# Sitara_IO_Bank_45.net
KiCad netlist of a schematic drawn in Altium Designer
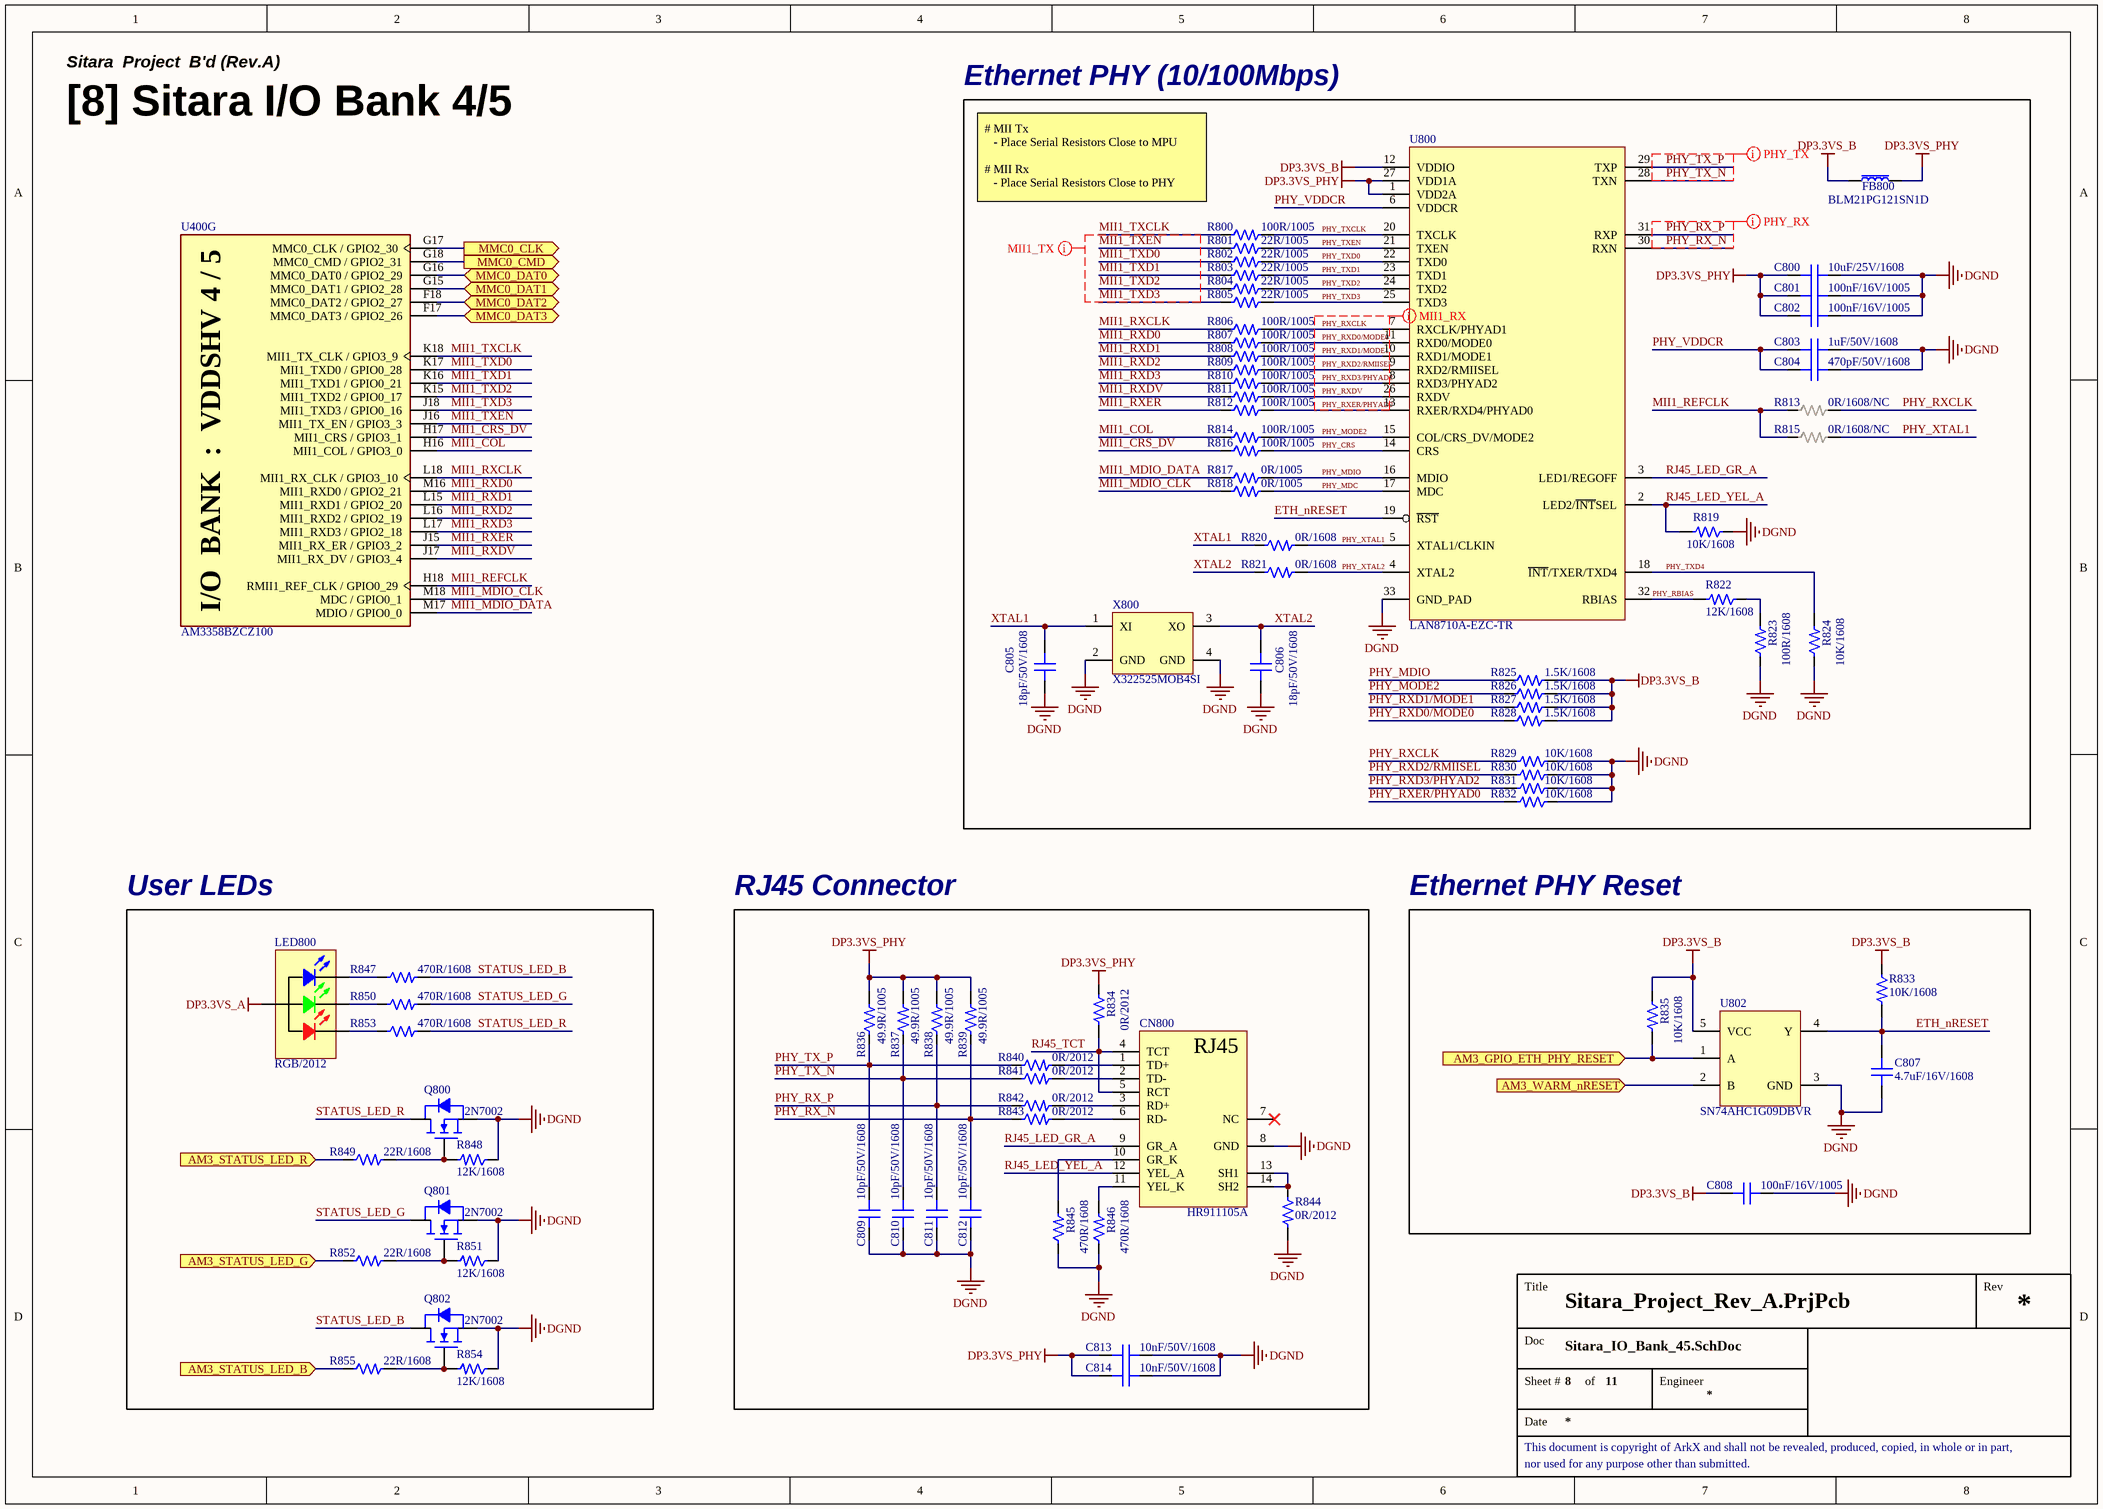
[diagram p0: Sitara_IO_Bank_45.SchDoc]

(export (version "E")
  (design (tool "Eeschema 10.0.6"))
  (components
    (comp (ref "C800")
      (value "10uF/25V/1608")
      (footprint "CAP 1608 (0603_INCH)")
      (description "Ceramic CAP_10uF/25V/1608")
      (fields (field (name "LCSC PART #") "C96446"))
      (libsource (lib "Arkx") (part "CAP_10uF/25V/1608"))
    )
    (comp (ref "C801")
      (value "100nF/16V/1005")
      (footprint "CAP 1005 (0402_INCH)")
      (description "Ceramic CAP_100nF/16V/1005")
      (fields (field (name "LCSC PART #") "C1525"))
      (libsource (lib "Arkx") (part "CAP_100nF/16V/1005"))
    )
    (comp (ref "C802")
      (value "100nF/16V/1005")
      (footprint "CAP 1005 (0402_INCH)")
      (description "Ceramic CAP_100nF/16V/1005")
      (fields (field (name "LCSC PART #") "C1525"))
      (libsource (lib "Arkx") (part "CAP_100nF/16V/1005"))
    )
    (comp (ref "C803")
      (value "1uF/50V/1608")
      (footprint "CAP 1608 (0603_INCH)")
      (description "Ceramic CAP_1uF/50V/1608")
      (fields (field (name "LCSC PART #") "C15849"))
      (libsource (lib "Arkx") (part "CAP_1uF/50V/1608"))
    )
    (comp (ref "C804")
      (value "470pF/50V/1608")
      (footprint "CAP 1608 (0603_INCH)")
      (description "Ceramic CAP_470pF/50V/1608")
      (fields (field (name "LCSC PART #") "C1620"))
      (libsource (lib "Arkx") (part "CAP_470pF/50V/1608"))
    )
    (comp (ref "C805")
      (value "18pF/50V/1608")
      (footprint "CAP 1608 (0603_INCH)")
      (description "Ceramic CAP_18pF/50V/1608")
      (fields (field (name "LCSC PART #") "C1647"))
      (libsource (lib "Arkx") (part "CAP_18pF/50V/1608"))
    )
    (comp (ref "C806")
      (value "18pF/50V/1608")
      (footprint "CAP 1608 (0603_INCH)")
      (description "Ceramic CAP_18pF/50V/1608")
      (fields (field (name "LCSC PART #") "C1647"))
      (libsource (lib "Arkx") (part "CAP_18pF/50V/1608"))
    )
    (comp (ref "C807")
      (value "4.7uF/16V/1608")
      (footprint "CAP 1608 (0603_INCH)")
      (description "Ceramic CAP_4.7uF/16V/1608")
      (fields (field (name "LCSC PART #") "C19666"))
      (libsource (lib "Arkx") (part "CAP_4.7uF/16V/1608"))
    )
    (comp (ref "C808")
      (value "100nF/16V/1005")
      (footprint "CAP 1005 (0402_INCH)")
      (description "Ceramic CAP_100nF/16V/1005")
      (fields (field (name "LCSC PART #") "C1525"))
      (libsource (lib "Arkx") (part "CAP_100nF/16V/1005"))
    )
    (comp (ref "C809")
      (value "10pF/50V/1608")
      (footprint "CAP 1608 (0603_INCH)")
      (description "Ceramic CAP_10pF/50V/1608")
      (fields (field (name "LCSC PART #") "C1634"))
      (libsource (lib "Arkx") (part "CAP_10pF/50V/1608"))
    )
    (comp (ref "C810")
      (value "10pF/50V/1608")
      (footprint "CAP 1608 (0603_INCH)")
      (description "Ceramic CAP_10pF/50V/1608")
      (fields (field (name "LCSC PART #") "C1634"))
      (libsource (lib "Arkx") (part "CAP_10pF/50V/1608"))
    )
    (comp (ref "C811")
      (value "10pF/50V/1608")
      (footprint "CAP 1608 (0603_INCH)")
      (description "Ceramic CAP_10pF/50V/1608")
      (fields (field (name "LCSC PART #") "C1634"))
      (libsource (lib "Arkx") (part "CAP_10pF/50V/1608"))
    )
    (comp (ref "C812")
      (value "10pF/50V/1608")
      (footprint "CAP 1608 (0603_INCH)")
      (description "Ceramic CAP_10pF/50V/1608")
      (fields (field (name "LCSC PART #") "C1634"))
      (libsource (lib "Arkx") (part "CAP_10pF/50V/1608"))
    )
    (comp (ref "C813")
      (value "10nF/50V/1608")
      (footprint "CAP 1608 (0603_INCH)")
      (description "Ceramic CAP_10nF/50V/1608")
      (fields (field (name "LCSC PART #") "C57112"))
      (libsource (lib "Arkx") (part "CAP_10nF/50V/1608"))
    )
    (comp (ref "C814")
      (value "10nF/50V/1608")
      (footprint "CAP 1608 (0603_INCH)")
      (description "Ceramic CAP_10nF/50V/1608")
      (fields (field (name "LCSC PART #") "C57112"))
      (libsource (lib "Arkx") (part "CAP_10nF/50V/1608"))
    )
    (comp (ref "CN800")
      (value "HR911105A")
      (footprint "CON_RJ45")
      (description "RJ45Receptacle 1 WithLED Plugin Ethernet Connectors / Modular Connectors (RJ45 RJ11) ROHS")
      (fields (field (name "LCSC PART #") "C12074"))
      (libsource (lib "Arkx") (part "CON_RJ45_HR911105A"))
    )
    (comp (ref "FB800")
      (value "BLM21PG121SN1D")
      (footprint "FB 2012 (0805_inch)")
      (description "3A 1 30mΩ 120Ω@100MHz ±25% 0805  Ferrite Beads ROHS")
      (fields (field (name "LCSC PART #") "C79382"))
      (libsource (lib "Arkx") (part "FB_BLM21PG121SN1D"))
    )
    (comp (ref "LED800")
      (value "RGB/2012")
      (footprint "LED MHT170RGBCT")
      (fields (field (name "LCSC PART #") "C2962094"))
      (libsource (lib "Arkx") (part "LED_RGB_MHT170RGBCT"))
    )
    (comp (ref "Q800")
      (value "2N7002")
      (footprint "SOT 23-3 (DIODES INCORPORATED)")
      (description "60V 115mA 200mW 7.5Ω@10V,500mA N Channel SOT-23  MOSFETs ROHS")
      (fields (field (name "LCSC PART #") "C8545"))
      (libsource (lib "Arkx") (part "FET_2N7002"))
    )
    (comp (ref "Q801")
      (value "2N7002")
      (footprint "SOT 23-3 (DIODES INCORPORATED)")
      (description "60V 115mA 200mW 7.5Ω@10V,500mA N Channel SOT-23  MOSFETs ROHS")
      (fields (field (name "LCSC PART #") "C8545"))
      (libsource (lib "Arkx") (part "FET_2N7002"))
    )
    (comp (ref "Q802")
      (value "2N7002")
      (footprint "SOT 23-3 (DIODES INCORPORATED)")
      (description "60V 115mA 200mW 7.5Ω@10V,500mA N Channel SOT-23  MOSFETs ROHS")
      (fields (field (name "LCSC PART #") "C8545"))
      (libsource (lib "Arkx") (part "FET_2N7002"))
    )
    (comp (ref "R800")
      (value "100R/1005")
      (footprint "RES 1005 (0402_inch)")
      (description "RES_100R/1005/62.5mW")
      (fields (field (name "LCSC PART #") "C25076"))
      (libsource (lib "Arkx") (part "RES_100R/1005/62.5mW"))
    )
    (comp (ref "R801")
      (value "22R/1005")
      (footprint "RES 1005 (0402_inch)")
      (description "RES_22R/1005/62.5mW")
      (fields (field (name "LCSC PART #") "C25092"))
      (libsource (lib "Arkx") (part "RES_22R/1005/62.5mW"))
    )
    (comp (ref "R802")
      (value "22R/1005")
      (footprint "RES 1005 (0402_inch)")
      (description "RES_22R/1005/62.5mW")
      (fields (field (name "LCSC PART #") "C25092"))
      (libsource (lib "Arkx") (part "RES_22R/1005/62.5mW"))
    )
    (comp (ref "R803")
      (value "22R/1005")
      (footprint "RES 1005 (0402_inch)")
      (description "RES_22R/1005/62.5mW")
      (fields (field (name "LCSC PART #") "C25092"))
      (libsource (lib "Arkx") (part "RES_22R/1005/62.5mW"))
    )
    (comp (ref "R804")
      (value "22R/1005")
      (footprint "RES 1005 (0402_inch)")
      (description "RES_22R/1005/62.5mW")
      (fields (field (name "LCSC PART #") "C25092"))
      (libsource (lib "Arkx") (part "RES_22R/1005/62.5mW"))
    )
    (comp (ref "R805")
      (value "22R/1005")
      (footprint "RES 1005 (0402_inch)")
      (description "RES_22R/1005/62.5mW")
      (fields (field (name "LCSC PART #") "C25092"))
      (libsource (lib "Arkx") (part "RES_22R/1005/62.5mW"))
    )
    (comp (ref "R806")
      (value "100R/1005")
      (footprint "RES 1005 (0402_inch)")
      (description "RES_100R/1005/62.5mW")
      (fields (field (name "LCSC PART #") "C25076"))
      (libsource (lib "Arkx") (part "RES_100R/1005/62.5mW"))
    )
    (comp (ref "R807")
      (value "100R/1005")
      (footprint "RES 1005 (0402_inch)")
      (description "RES_100R/1005/62.5mW")
      (fields (field (name "LCSC PART #") "C25076"))
      (libsource (lib "Arkx") (part "RES_100R/1005/62.5mW"))
    )
    (comp (ref "R808")
      (value "100R/1005")
      (footprint "RES 1005 (0402_inch)")
      (description "RES_100R/1005/62.5mW")
      (fields (field (name "LCSC PART #") "C25076"))
      (libsource (lib "Arkx") (part "RES_100R/1005/62.5mW"))
    )
    (comp (ref "R809")
      (value "100R/1005")
      (footprint "RES 1005 (0402_inch)")
      (description "RES_100R/1005/62.5mW")
      (fields (field (name "LCSC PART #") "C25076"))
      (libsource (lib "Arkx") (part "RES_100R/1005/62.5mW"))
    )
    (comp (ref "R810")
      (value "100R/1005")
      (footprint "RES 1005 (0402_inch)")
      (description "RES_100R/1005/62.5mW")
      (fields (field (name "LCSC PART #") "C25076"))
      (libsource (lib "Arkx") (part "RES_100R/1005/62.5mW"))
    )
    (comp (ref "R811")
      (value "100R/1005")
      (footprint "RES 1005 (0402_inch)")
      (description "RES_100R/1005/62.5mW")
      (fields (field (name "LCSC PART #") "C25076"))
      (libsource (lib "Arkx") (part "RES_100R/1005/62.5mW"))
    )
    (comp (ref "R812")
      (value "100R/1005")
      (footprint "RES 1005 (0402_inch)")
      (description "RES_100R/1005/62.5mW")
      (fields (field (name "LCSC PART #") "C25076"))
      (libsource (lib "Arkx") (part "RES_100R/1005/62.5mW"))
    )
    (comp (ref "R813")
      (value "0R/1608/NC")
      (footprint "RES 1608 (0603_inch)/NC")
      (description "0R/1608/0.1W/NC")
      (libsource (lib "Arkx") (part "RES_NC_0R/1608/0.1W"))
    )
    (comp (ref "R814")
      (value "100R/1005")
      (footprint "RES 1005 (0402_inch)")
      (description "RES_100R/1005/62.5mW")
      (fields (field (name "LCSC PART #") "C25076"))
      (libsource (lib "Arkx") (part "RES_100R/1005/62.5mW"))
    )
    (comp (ref "R815")
      (value "0R/1608/NC")
      (footprint "RES 1608 (0603_inch)/NC")
      (description "0R/1608/0.1W/NC")
      (libsource (lib "Arkx") (part "RES_NC_0R/1608/0.1W"))
    )
    (comp (ref "R816")
      (value "100R/1005")
      (footprint "RES 1005 (0402_inch)")
      (description "RES_100R/1005/62.5mW")
      (fields (field (name "LCSC PART #") "C25076"))
      (libsource (lib "Arkx") (part "RES_100R/1005/62.5mW"))
    )
    (comp (ref "R817")
      (value "0R/1005")
      (footprint "RES 1005 (0402_inch)")
      (description "RES_0R/1005/62.5mW")
      (fields (field (name "LCSC PART #") "C17168"))
      (libsource (lib "Arkx") (part "RES_0R/1005/62.5mW"))
    )
    (comp (ref "R818")
      (value "0R/1005")
      (footprint "RES 1005 (0402_inch)")
      (description "RES_0R/1005/62.5mW")
      (fields (field (name "LCSC PART #") "C17168"))
      (libsource (lib "Arkx") (part "RES_0R/1005/62.5mW"))
    )
    (comp (ref "R819")
      (value "10K/1608")
      (footprint "RES 1608 (0603_inch)")
      (description "RES_10K/1608/0.1W")
      (fields (field (name "LCSC PART #") "C25804"))
      (libsource (lib "Arkx") (part "RES_10K/1608/0.1W"))
    )
    (comp (ref "R820")
      (value "0R/1608")
      (footprint "RES 1608 (0603_inch)")
      (description "RES_0R/1608/0.1W")
      (fields (field (name "LCSC PART #") "C21189"))
      (libsource (lib "Arkx") (part "RES_0R/1608/0.1W"))
    )
    (comp (ref "R821")
      (value "0R/1608")
      (footprint "RES 1608 (0603_inch)")
      (description "RES_0R/1608/0.1W")
      (fields (field (name "LCSC PART #") "C21189"))
      (libsource (lib "Arkx") (part "RES_0R/1608/0.1W"))
    )
    (comp (ref "R822")
      (value "12K/1608")
      (footprint "RES 1608 (0603_inch)")
      (description "RES_12K/1608/0.1W")
      (fields (field (name "LCSC PART #") "C22790"))
      (libsource (lib "Arkx") (part "RES_12K/1608/0.1W"))
    )
    (comp (ref "R823")
      (value "100R/1608")
      (footprint "RES 1608 (0603_inch)")
      (description "RES_100R/1608/0.1W")
      (fields (field (name "LCSC PART #") "C22775"))
      (libsource (lib "Arkx") (part "RES_100R/1608/0.1W"))
    )
    (comp (ref "R824")
      (value "10K/1608")
      (footprint "RES 1608 (0603_inch)")
      (description "RES_10K/1608/0.1W")
      (fields (field (name "LCSC PART #") "C25804"))
      (libsource (lib "Arkx") (part "RES_10K/1608/0.1W"))
    )
    (comp (ref "R825")
      (value "1.5K/1608")
      (footprint "RES 1608 (0603_inch)")
      (description "RES_1.5K/1608/0.1W")
      (fields (field (name "LCSC PART #") "C22843"))
      (libsource (lib "Arkx") (part "RES_1.5K/1608/0.1W"))
    )
    (comp (ref "R826")
      (value "1.5K/1608")
      (footprint "RES 1608 (0603_inch)")
      (description "RES_1.5K/1608/0.1W")
      (fields (field (name "LCSC PART #") "C22843"))
      (libsource (lib "Arkx") (part "RES_1.5K/1608/0.1W"))
    )
    (comp (ref "R827")
      (value "1.5K/1608")
      (footprint "RES 1608 (0603_inch)")
      (description "RES_1.5K/1608/0.1W")
      (fields (field (name "LCSC PART #") "C22843"))
      (libsource (lib "Arkx") (part "RES_1.5K/1608/0.1W"))
    )
    (comp (ref "R828")
      (value "1.5K/1608")
      (footprint "RES 1608 (0603_inch)")
      (description "RES_1.5K/1608/0.1W")
      (fields (field (name "LCSC PART #") "C22843"))
      (libsource (lib "Arkx") (part "RES_1.5K/1608/0.1W"))
    )
    (comp (ref "R829")
      (value "10K/1608")
      (footprint "RES 1608 (0603_inch)")
      (description "RES_10K/1608/0.1W")
      (fields (field (name "LCSC PART #") "C25804"))
      (libsource (lib "Arkx") (part "RES_10K/1608/0.1W"))
    )
    (comp (ref "R830")
      (value "10K/1608")
      (footprint "RES 1608 (0603_inch)")
      (description "RES_10K/1608/0.1W")
      (fields (field (name "LCSC PART #") "C25804"))
      (libsource (lib "Arkx") (part "RES_10K/1608/0.1W"))
    )
    (comp (ref "R831")
      (value "10K/1608")
      (footprint "RES 1608 (0603_inch)")
      (description "RES_10K/1608/0.1W")
      (fields (field (name "LCSC PART #") "C25804"))
      (libsource (lib "Arkx") (part "RES_10K/1608/0.1W"))
    )
    (comp (ref "R832")
      (value "10K/1608")
      (footprint "RES 1608 (0603_inch)")
      (description "RES_10K/1608/0.1W")
      (fields (field (name "LCSC PART #") "C25804"))
      (libsource (lib "Arkx") (part "RES_10K/1608/0.1W"))
    )
    (comp (ref "R833")
      (value "10K/1608")
      (footprint "RES 1608 (0603_inch)")
      (description "RES_10K/1608/0.1W")
      (fields (field (name "LCSC PART #") "C25804"))
      (libsource (lib "Arkx") (part "RES_10K/1608/0.1W"))
    )
    (comp (ref "R834")
      (value "0R/2012")
      (footprint "RES 2012 (0805_inch)")
      (description "RES_0R/2012/0.125W")
      (fields (field (name "LCSC PART #") "C17477"))
      (libsource (lib "Arkx") (part "RES_0R/2012/0.125W"))
    )
    (comp (ref "R835")
      (value "10K/1608")
      (footprint "RES 1608 (0603_inch)")
      (description "RES_10K/1608/0.1W")
      (fields (field (name "LCSC PART #") "C25804"))
      (libsource (lib "Arkx") (part "RES_10K/1608/0.1W"))
    )
    (comp (ref "R836")
      (value "49.9R/1005")
      (footprint "RES 1005 (0402_inch)")
      (description "RES_49.9R/1005/62.5mW")
      (fields (field (name "LCSC PART #") "C25120"))
      (libsource (lib "Arkx") (part "RES_49.9R/1005/62.5mW"))
    )
    (comp (ref "R837")
      (value "49.9R/1005")
      (footprint "RES 1005 (0402_inch)")
      (description "RES_49.9R/1005/62.5mW")
      (fields (field (name "LCSC PART #") "C25120"))
      (libsource (lib "Arkx") (part "RES_49.9R/1005/62.5mW"))
    )
    (comp (ref "R838")
      (value "49.9R/1005")
      (footprint "RES 1005 (0402_inch)")
      (description "RES_49.9R/1005/62.5mW")
      (fields (field (name "LCSC PART #") "C25120"))
      (libsource (lib "Arkx") (part "RES_49.9R/1005/62.5mW"))
    )
    (comp (ref "R839")
      (value "49.9R/1005")
      (footprint "RES 1005 (0402_inch)")
      (description "RES_49.9R/1005/62.5mW")
      (fields (field (name "LCSC PART #") "C25120"))
      (libsource (lib "Arkx") (part "RES_49.9R/1005/62.5mW"))
    )
    (comp (ref "R840")
      (value "0R/2012")
      (footprint "RES 2012 (0805_inch)")
      (description "RES_0R/2012/0.125W")
      (fields (field (name "LCSC PART #") "C17477"))
      (libsource (lib "Arkx") (part "RES_0R/2012/0.125W"))
    )
    (comp (ref "R841")
      (value "0R/2012")
      (footprint "RES 2012 (0805_inch)")
      (description "RES_0R/2012/0.125W")
      (fields (field (name "LCSC PART #") "C17477"))
      (libsource (lib "Arkx") (part "RES_0R/2012/0.125W"))
    )
    (comp (ref "R842")
      (value "0R/2012")
      (footprint "RES 2012 (0805_inch)")
      (description "RES_0R/2012/0.125W")
      (fields (field (name "LCSC PART #") "C17477"))
      (libsource (lib "Arkx") (part "RES_0R/2012/0.125W"))
    )
    (comp (ref "R843")
      (value "0R/2012")
      (footprint "RES 2012 (0805_inch)")
      (description "RES_0R/2012/0.125W")
      (fields (field (name "LCSC PART #") "C17477"))
      (libsource (lib "Arkx") (part "RES_0R/2012/0.125W"))
    )
    (comp (ref "R844")
      (value "0R/2012")
      (footprint "RES 2012 (0805_inch)")
      (description "RES_0R/2012/0.125W")
      (fields (field (name "LCSC PART #") "C17477"))
      (libsource (lib "Arkx") (part "RES_0R/2012/0.125W"))
    )
    (comp (ref "R845")
      (value "470R/1608")
      (footprint "RES 1608 (0603_inch)")
      (description "RES_470R/1608/0.1W")
      (fields (field (name "LCSC PART #") "C23179"))
      (libsource (lib "Arkx") (part "RES_470R/1608/0.1W"))
    )
    (comp (ref "R846")
      (value "470R/1608")
      (footprint "RES 1608 (0603_inch)")
      (description "RES_470R/1608/0.1W")
      (fields (field (name "LCSC PART #") "C23179"))
      (libsource (lib "Arkx") (part "RES_470R/1608/0.1W"))
    )
    (comp (ref "R847")
      (value "470R/1608")
      (footprint "RES 1608 (0603_inch)")
      (description "RES_470R/1608/0.1W")
      (fields (field (name "LCSC PART #") "C23179"))
      (libsource (lib "Arkx") (part "RES_470R/1608/0.1W"))
    )
    (comp (ref "R848")
      (value "12K/1608")
      (footprint "RES 1608 (0603_inch)")
      (description "RES_12K/1608/0.1W")
      (fields (field (name "LCSC PART #") "C22790"))
      (libsource (lib "Arkx") (part "RES_12K/1608/0.1W"))
    )
    (comp (ref "R849")
      (value "22R/1608")
      (footprint "RES 1608 (0603_inch)")
      (description "RES_22R/1608/0.1W")
      (fields (field (name "LCSC PART #") "C23345"))
      (libsource (lib "Arkx") (part "RES_22R/1608/0.1W"))
    )
    (comp (ref "R850")
      (value "470R/1608")
      (footprint "RES 1608 (0603_inch)")
      (description "RES_470R/1608/0.1W")
      (fields (field (name "LCSC PART #") "C23179"))
      (libsource (lib "Arkx") (part "RES_470R/1608/0.1W"))
    )
    (comp (ref "R851")
      (value "12K/1608")
      (footprint "RES 1608 (0603_inch)")
      (description "RES_12K/1608/0.1W")
      (fields (field (name "LCSC PART #") "C22790"))
      (libsource (lib "Arkx") (part "RES_12K/1608/0.1W"))
    )
    (comp (ref "R852")
      (value "22R/1608")
      (footprint "RES 1608 (0603_inch)")
      (description "RES_22R/1608/0.1W")
      (fields (field (name "LCSC PART #") "C23345"))
      (libsource (lib "Arkx") (part "RES_22R/1608/0.1W"))
    )
    (comp (ref "R853")
      (value "470R/1608")
      (footprint "RES 1608 (0603_inch)")
      (description "RES_470R/1608/0.1W")
      (fields (field (name "LCSC PART #") "C23179"))
      (libsource (lib "Arkx") (part "RES_470R/1608/0.1W"))
    )
    (comp (ref "R854")
      (value "12K/1608")
      (footprint "RES 1608 (0603_inch)")
      (description "RES_12K/1608/0.1W")
      (fields (field (name "LCSC PART #") "C22790"))
      (libsource (lib "Arkx") (part "RES_12K/1608/0.1W"))
    )
    (comp (ref "R855")
      (value "22R/1608")
      (footprint "RES 1608 (0603_inch)")
      (description "RES_22R/1608/0.1W")
      (fields (field (name "LCSC PART #") "C23345"))
      (libsource (lib "Arkx") (part "RES_22R/1608/0.1W"))
    )
    (comp (ref "U400")
      (value "AM3358BZCZ100")
      (footprint "IC_SOC_AM3358BZCZ100")
      (description "ARM® Cortex®-A8 Microprocessor IC Sitara™ 1 Core, 32-Bit 1.0GHz 324-NFBGA (15x15)")
      (fields (field (name "LCSC PART #") "C73932"))
      (libsource (lib "Arkx") (part "IC_SOC_AM3358BZCZ100"))
    )
    (comp (ref "U800")
      (value "LAN8710A-EZC-TR")
      (footprint "IC_QFN-32 (5x5)")
      (description "4/4 Transceiver Full MII, RMII 32-QFN (5x5)")
      (fields (field (name "LCSC PART #") "C46185"))
      (libsource (lib "Arkx") (part "IC_ETH_LAN8710A-EZC-TR"))
    )
    (comp (ref "U802")
      (value "SN74AHC1G09DBVR")
      (footprint "SOT-23-5 (TI DBV PACKAGE)")
      (description "AND Gate IC 1 Channel Open Drain SOT-23-5")
      (fields (field (name "LCSC PART #") "C840099"))
      (libsource (lib "Arkx") (part "IC_AND_SN74AHC1G09DBVR"))
    )
    (comp (ref "X800")
      (value "X322525MOB4SI")
      (footprint "OSC_SMD_3.2x2.5(YXC)")
      (description "25MHz Surface Mount Crystal 12pF ±10ppm ±20ppm SMD3225-4P Crystals ROHS")
      (fields (field (name "LCSC PART #") "C9006"))
      (libsource (lib "Arkx") (part "XTAL_25MHz_X322525MOB4SI"))
    )
  )
  (nets
    (net (code "1") (name "/AM3_GPIO_ETH_PHY_RESET") (class "Default")
      (node (ref "R835") (pin "2") (pinfunction "2_2") (pintype "passive"))
      (node (ref "U802") (pin "1") (pinfunction "A_1") (pintype "passive"))
    )
    (net (code "2") (name "/AM3_STATUS_LED_B") (class "Default")
      (node (ref "R855") (pin "1") (pinfunction "1_1") (pintype "passive"))
    )
    (net (code "3") (name "/AM3_STATUS_LED_G") (class "Default")
      (node (ref "R852") (pin "1") (pinfunction "1_1") (pintype "passive"))
    )
    (net (code "4") (name "/AM3_STATUS_LED_R") (class "Default")
      (node (ref "R849") (pin "1") (pinfunction "1_1") (pintype "passive"))
    )
    (net (code "5") (name "/AM3_WARM_nRESET") (class "Default")
      (node (ref "U802") (pin "2") (pinfunction "B_2") (pintype "passive"))
    )
    (net (code "6") (name "/ETH_nRESET") (class "Default")
      (node (ref "C807") (pin "2") (pinfunction "2_2") (pintype "passive"))
      (node (ref "R833") (pin "2") (pinfunction "2_2") (pintype "passive"))
      (node (ref "U800") (pin "19") (pinfunction "~{RST}_19") (pintype "passive"))
      (node (ref "U802") (pin "4") (pinfunction "Y_4") (pintype "passive"))
    )
    (net (code "7") (name "/MII1_COL") (class "Default")
      (node (ref "R814") (pin "1") (pinfunction "1_1") (pintype "passive"))
      (node (ref "U400") (pin "H16") (pinfunction "MII1_COL_/_GPIO3_0_H16") (pintype "passive"))
    )
    (net (code "8") (name "/MII1_CRS_DV") (class "Default")
      (node (ref "R816") (pin "1") (pinfunction "1_1") (pintype "passive"))
      (node (ref "U400") (pin "H17") (pinfunction "MII1_CRS_/_GPIO3_1_H17") (pintype "passive"))
    )
    (net (code "9") (name "/MII1_MDIO_CLK") (class "Default")
      (node (ref "R818") (pin "1") (pinfunction "1_1") (pintype "passive"))
      (node (ref "U400") (pin "M18") (pinfunction "MDC_/_GPIO0_1_M18") (pintype "passive"))
    )
    (net (code "10") (name "/MII1_MDIO_DATA") (class "Default")
      (node (ref "R817") (pin "1") (pinfunction "1_1") (pintype "passive"))
      (node (ref "U400") (pin "M17") (pinfunction "MDIO_/_GPIO0_0_M17") (pintype "passive"))
    )
    (net (code "11") (name "/MII1_REFCLK") (class "Default")
      (node (ref "R813") (pin "1") (pinfunction "1_1") (pintype "passive"))
      (node (ref "R815") (pin "1") (pinfunction "1_1") (pintype "passive"))
      (node (ref "U400") (pin "H18") (pinfunction "RMII1_REF_CLK_/_GPIO0_29_H18") (pintype "passive"))
    )
    (net (code "12") (name "/MII1_RXCLK") (class "Default")
      (node (ref "R806") (pin "1") (pinfunction "1_1") (pintype "passive"))
      (node (ref "U400") (pin "L18") (pinfunction "MII1_RX_CLK_/_GPIO3_10_L18") (pintype "passive"))
    )
    (net (code "13") (name "/MII1_RXD0") (class "Default")
      (node (ref "R807") (pin "1") (pinfunction "1_1") (pintype "passive"))
      (node (ref "U400") (pin "M16") (pinfunction "MII1_RXD0_/_GPIO2_21_M16") (pintype "passive"))
    )
    (net (code "14") (name "/MII1_RXD1") (class "Default")
      (node (ref "R808") (pin "1") (pinfunction "1_1") (pintype "passive"))
      (node (ref "U400") (pin "L15") (pinfunction "MII1_RXD1_/_GPIO2_20_L15") (pintype "passive"))
    )
    (net (code "15") (name "/MII1_RXD2") (class "Default")
      (node (ref "R809") (pin "1") (pinfunction "1_1") (pintype "passive"))
      (node (ref "U400") (pin "L16") (pinfunction "MII1_RXD2_/_GPIO2_19_L16") (pintype "passive"))
    )
    (net (code "16") (name "/MII1_RXD3") (class "Default")
      (node (ref "R810") (pin "1") (pinfunction "1_1") (pintype "passive"))
      (node (ref "U400") (pin "L17") (pinfunction "MII1_RXD3_/_GPIO2_18_L17") (pintype "passive"))
    )
    (net (code "17") (name "/MII1_RXDV") (class "Default")
      (node (ref "R811") (pin "1") (pinfunction "1_1") (pintype "passive"))
      (node (ref "U400") (pin "J17") (pinfunction "MII1_RX_DV_/_GPIO3_4_J17") (pintype "passive"))
    )
    (net (code "18") (name "/MII1_RXER") (class "Default")
      (node (ref "R812") (pin "1") (pinfunction "1_1") (pintype "passive"))
      (node (ref "U400") (pin "J15") (pinfunction "MII1_RX_ER_/_GPIO3_2_J15") (pintype "passive"))
    )
    (net (code "19") (name "/MII1_TXCLK") (class "Default")
      (node (ref "R800") (pin "1") (pinfunction "1_1") (pintype "passive"))
      (node (ref "U400") (pin "K18") (pinfunction "MII1_TX_CLK_/_GPIO3_9_K18") (pintype "passive"))
    )
    (net (code "20") (name "/MII1_TXD0") (class "Default")
      (node (ref "R802") (pin "1") (pinfunction "1_1") (pintype "passive"))
      (node (ref "U400") (pin "K17") (pinfunction "MII1_TXD0_/_GPIO0_28_K17") (pintype "passive"))
    )
    (net (code "21") (name "/MII1_TXD1") (class "Default")
      (node (ref "R803") (pin "1") (pinfunction "1_1") (pintype "passive"))
      (node (ref "U400") (pin "K16") (pinfunction "MII1_TXD1_/_GPIO0_21_K16") (pintype "passive"))
    )
    (net (code "22") (name "/MII1_TXD2") (class "Default")
      (node (ref "R804") (pin "1") (pinfunction "1_1") (pintype "passive"))
      (node (ref "U400") (pin "K15") (pinfunction "MII1_TXD2_/_GPIO0_17_K15") (pintype "passive"))
    )
    (net (code "23") (name "/MII1_TXD3") (class "Default")
      (node (ref "R805") (pin "1") (pinfunction "1_1") (pintype "passive"))
      (node (ref "U400") (pin "J18") (pinfunction "MII1_TXD3_/_GPIO0_16_J18") (pintype "passive"))
    )
    (net (code "24") (name "/MII1_TXEN") (class "Default")
      (node (ref "R801") (pin "1") (pinfunction "1_1") (pintype "passive"))
      (node (ref "U400") (pin "J16") (pinfunction "MII1_TX_EN_/_GPIO3_3_J16") (pintype "passive"))
    )
    (net (code "25") (name "/MMC0_CLK") (class "Default")
      (node (ref "U400") (pin "G17") (pinfunction "MMC0_CLK_/_GPIO2_30_G17") (pintype "passive"))
    )
    (net (code "26") (name "/MMC0_CMD") (class "Default")
      (node (ref "U400") (pin "G18") (pinfunction "MMC0_CMD_/_GPIO2_31_G18") (pintype "passive"))
    )
    (net (code "27") (name "/MMC0_DAT0") (class "Default")
      (node (ref "U400") (pin "G16") (pinfunction "MMC0_DAT0_/_GPIO2_29_G16") (pintype "passive"))
    )
    (net (code "28") (name "/MMC0_DAT1") (class "Default")
      (node (ref "U400") (pin "G15") (pinfunction "MMC0_DAT1_/_GPIO2_28_G15") (pintype "passive"))
    )
    (net (code "29") (name "/MMC0_DAT2") (class "Default")
      (node (ref "U400") (pin "F18") (pinfunction "MMC0_DAT2_/_GPIO2_27_F18") (pintype "passive"))
    )
    (net (code "30") (name "/MMC0_DAT3") (class "Default")
      (node (ref "U400") (pin "F17") (pinfunction "MMC0_DAT3_/_GPIO2_26_F17") (pintype "passive"))
    )
    (net (code "31") (name "/PHY_CRS") (class "Default")
      (node (ref "R816") (pin "2") (pinfunction "2_2") (pintype "passive"))
      (node (ref "U800") (pin "14") (pinfunction "CRS_14") (pintype "passive"))
    )
    (net (code "32") (name "/PHY_MDC") (class "Default")
      (node (ref "R818") (pin "2") (pinfunction "2_2") (pintype "passive"))
      (node (ref "U800") (pin "17") (pinfunction "MDC_17") (pintype "passive"))
    )
    (net (code "33") (name "/PHY_MDIO") (class "Default")
      (node (ref "R817") (pin "2") (pinfunction "2_2") (pintype "passive"))
      (node (ref "R825") (pin "1") (pinfunction "1_1") (pintype "passive"))
      (node (ref "U800") (pin "16") (pinfunction "MDIO_16") (pintype "passive"))
    )
    (net (code "34") (name "/PHY_MODE2") (class "Default")
      (node (ref "R814") (pin "2") (pinfunction "2_2") (pintype "passive"))
      (node (ref "R826") (pin "1") (pinfunction "1_1") (pintype "passive"))
      (node (ref "U800") (pin "15") (pinfunction "COL/CRS_DV/MODE2_15") (pintype "passive"))
    )
    (net (code "35") (name "/PHY_RBIAS") (class "Default")
      (node (ref "R822") (pin "2") (pinfunction "2_2") (pintype "passive"))
      (node (ref "U800") (pin "32") (pinfunction "RBIAS_32") (pintype "passive"))
    )
    (net (code "36") (name "/PHY_RXCLK") (class "Default")
      (node (ref "R806") (pin "2") (pinfunction "2_2") (pintype "passive"))
      (node (ref "R813") (pin "2") (pinfunction "2_2") (pintype "passive"))
      (node (ref "R829") (pin "2") (pinfunction "2_2") (pintype "passive"))
      (node (ref "U800") (pin "7") (pinfunction "RXCLK/PHYAD1_7") (pintype "passive"))
    )
    (net (code "37") (name "/PHY_RXD0{slash}MODE0") (class "Default")
      (node (ref "R807") (pin "2") (pinfunction "2_2") (pintype "passive"))
      (node (ref "R828") (pin "1") (pinfunction "1_1") (pintype "passive"))
      (node (ref "U800") (pin "11") (pinfunction "RXD0/MODE0_11") (pintype "passive"))
    )
    (net (code "38") (name "/PHY_RXD1{slash}MODE1") (class "Default")
      (node (ref "R808") (pin "2") (pinfunction "2_2") (pintype "passive"))
      (node (ref "R827") (pin "1") (pinfunction "1_1") (pintype "passive"))
      (node (ref "U800") (pin "10") (pinfunction "RXD1/MODE1_10") (pintype "passive"))
    )
    (net (code "39") (name "/PHY_RXD2{slash}RMIISEL") (class "Default")
      (node (ref "R809") (pin "2") (pinfunction "2_2") (pintype "passive"))
      (node (ref "R830") (pin "2") (pinfunction "2_2") (pintype "passive"))
      (node (ref "U800") (pin "9") (pinfunction "RXD2/RMIISEL_9") (pintype "passive"))
    )
    (net (code "40") (name "/PHY_RXD3{slash}PHYAD2") (class "Default")
      (node (ref "R810") (pin "2") (pinfunction "2_2") (pintype "passive"))
      (node (ref "R831") (pin "2") (pinfunction "2_2") (pintype "passive"))
      (node (ref "U800") (pin "8") (pinfunction "RXD3/PHYAD2_8") (pintype "passive"))
    )
    (net (code "41") (name "/PHY_RXDV") (class "Default")
      (node (ref "R811") (pin "2") (pinfunction "2_2") (pintype "passive"))
      (node (ref "U800") (pin "26") (pinfunction "RXDV_26") (pintype "passive"))
    )
    (net (code "42") (name "/PHY_RXER{slash}PHYAD0") (class "Default")
      (node (ref "R812") (pin "2") (pinfunction "2_2") (pintype "passive"))
      (node (ref "R832") (pin "2") (pinfunction "2_2") (pintype "passive"))
      (node (ref "U800") (pin "13") (pinfunction "RXER/RXD4/PHYAD0_13") (pintype "passive"))
    )
    (net (code "43") (name "/PHY_RX_N") (class "Default")
      (node (ref "C812") (pin "2") (pinfunction "2_2") (pintype "passive"))
      (node (ref "R839") (pin "1") (pinfunction "1_1") (pintype "passive"))
      (node (ref "R843") (pin "1") (pinfunction "1_1") (pintype "passive"))
      (node (ref "U800") (pin "30") (pinfunction "RXN_30") (pintype "passive"))
    )
    (net (code "44") (name "/PHY_RX_P") (class "Default")
      (node (ref "C811") (pin "2") (pinfunction "2_2") (pintype "passive"))
      (node (ref "R838") (pin "1") (pinfunction "1_1") (pintype "passive"))
      (node (ref "R842") (pin "1") (pinfunction "1_1") (pintype "passive"))
      (node (ref "U800") (pin "31") (pinfunction "RXP_31") (pintype "passive"))
    )
    (net (code "45") (name "/PHY_TXCLK") (class "Default")
      (node (ref "R800") (pin "2") (pinfunction "2_2") (pintype "passive"))
      (node (ref "U800") (pin "20") (pinfunction "TXCLK_20") (pintype "passive"))
    )
    (net (code "46") (name "/PHY_TXD0") (class "Default")
      (node (ref "R802") (pin "2") (pinfunction "2_2") (pintype "passive"))
      (node (ref "U800") (pin "22") (pinfunction "TXD0_22") (pintype "passive"))
    )
    (net (code "47") (name "/PHY_TXD1") (class "Default")
      (node (ref "R803") (pin "2") (pinfunction "2_2") (pintype "passive"))
      (node (ref "U800") (pin "23") (pinfunction "TXD1_23") (pintype "passive"))
    )
    (net (code "48") (name "/PHY_TXD2") (class "Default")
      (node (ref "R804") (pin "2") (pinfunction "2_2") (pintype "passive"))
      (node (ref "U800") (pin "24") (pinfunction "TXD2_24") (pintype "passive"))
    )
    (net (code "49") (name "/PHY_TXD3") (class "Default")
      (node (ref "R805") (pin "2") (pinfunction "2_2") (pintype "passive"))
      (node (ref "U800") (pin "25") (pinfunction "TXD3_25") (pintype "passive"))
    )
    (net (code "50") (name "/PHY_TXD4") (class "Default")
      (node (ref "R824") (pin "2") (pinfunction "2_2") (pintype "passive"))
      (node (ref "U800") (pin "18") (pinfunction "~{INT}/TXER/TXD4_18") (pintype "passive"))
    )
    (net (code "51") (name "/PHY_TXEN") (class "Default")
      (node (ref "R801") (pin "2") (pinfunction "2_2") (pintype "passive"))
      (node (ref "U800") (pin "21") (pinfunction "TXEN_21") (pintype "passive"))
    )
    (net (code "52") (name "/PHY_TX_N") (class "Default")
      (node (ref "C810") (pin "2") (pinfunction "2_2") (pintype "passive"))
      (node (ref "R837") (pin "1") (pinfunction "1_1") (pintype "passive"))
      (node (ref "R841") (pin "1") (pinfunction "1_1") (pintype "passive"))
      (node (ref "U800") (pin "28") (pinfunction "TXN_28") (pintype "passive"))
    )
    (net (code "53") (name "/PHY_TX_P") (class "Default")
      (node (ref "C809") (pin "2") (pinfunction "2_2") (pintype "passive"))
      (node (ref "R836") (pin "1") (pinfunction "1_1") (pintype "passive"))
      (node (ref "R840") (pin "1") (pinfunction "1_1") (pintype "passive"))
      (node (ref "U800") (pin "29") (pinfunction "TXP_29") (pintype "passive"))
    )
    (net (code "54") (name "/PHY_VDDCR") (class "Default")
      (node (ref "C803") (pin "1") (pinfunction "1_1") (pintype "passive"))
      (node (ref "C804") (pin "1") (pinfunction "1_1") (pintype "passive"))
      (node (ref "U800") (pin "6") (pinfunction "VDDCR_6") (pintype "passive"))
    )
    (net (code "55") (name "/PHY_XTAL1") (class "Default")
      (node (ref "R815") (pin "2") (pinfunction "2_2") (pintype "passive"))
      (node (ref "R820") (pin "2") (pinfunction "2_2") (pintype "passive"))
      (node (ref "U800") (pin "5") (pinfunction "XTAL1/CLKIN_5") (pintype "passive"))
    )
    (net (code "56") (name "/PHY_XTAL2") (class "Default")
      (node (ref "R821") (pin "2") (pinfunction "2_2") (pintype "passive"))
      (node (ref "U800") (pin "4") (pinfunction "XTAL2_4") (pintype "passive"))
    )
    (net (code "57") (name "/RJ45_LED_GR_A") (class "Default")
      (node (ref "CN800") (pin "9") (pinfunction "GR_A_9") (pintype "passive"))
      (node (ref "U800") (pin "3") (pinfunction "LED1/REGOFF_3") (pintype "passive"))
    )
    (net (code "58") (name "/RJ45_LED_YEL_A") (class "Default")
      (node (ref "CN800") (pin "12") (pinfunction "YEL_A_12") (pintype "passive"))
      (node (ref "R819") (pin "2") (pinfunction "2_2") (pintype "passive"))
      (node (ref "U800") (pin "2") (pinfunction "LED2/~{INT}SEL_2") (pintype "passive"))
    )
    (net (code "59") (name "/RJ45_TCT") (class "Default")
      (node (ref "CN800") (pin "4") (pinfunction "TCT_4") (pintype "passive"))
      (node (ref "CN800") (pin "5") (pinfunction "RCT_5") (pintype "passive"))
      (node (ref "R834") (pin "2") (pinfunction "2_2") (pintype "passive"))
    )
    (net (code "60") (name "/STATUS_LED_B") (class "Default")
      (node (ref "Q802") (pin "3") (pinfunction "D_3") (pintype "passive"))
      (node (ref "R847") (pin "2") (pinfunction "2_2") (pintype "passive"))
    )
    (net (code "61") (name "/STATUS_LED_G") (class "Default")
      (node (ref "Q801") (pin "3") (pinfunction "D_3") (pintype "passive"))
      (node (ref "R850") (pin "2") (pinfunction "2_2") (pintype "passive"))
    )
    (net (code "62") (name "/STATUS_LED_R") (class "Default")
      (node (ref "Q800") (pin "3") (pinfunction "D_3") (pintype "passive"))
      (node (ref "R853") (pin "2") (pinfunction "2_2") (pintype "passive"))
    )
    (net (code "63") (name "/XTAL1") (class "Default")
      (node (ref "C805") (pin "2") (pinfunction "2_2") (pintype "passive"))
      (node (ref "R820") (pin "1") (pinfunction "1_1") (pintype "passive"))
      (node (ref "X800") (pin "1") (pinfunction "XI_1") (pintype "passive"))
    )
    (net (code "64") (name "/XTAL2") (class "Default")
      (node (ref "C806") (pin "2") (pinfunction "2_2") (pintype "passive"))
      (node (ref "R821") (pin "1") (pinfunction "1_1") (pintype "passive"))
      (node (ref "X800") (pin "3") (pinfunction "XO_3") (pintype "passive"))
    )
    (net (code "65") (name "DGND") (class "Default")
      (node (ref "C800") (pin "2") (pinfunction "2_2") (pintype "passive"))
      (node (ref "C801") (pin "2") (pinfunction "2_2") (pintype "passive"))
      (node (ref "C802") (pin "2") (pinfunction "2_2") (pintype "passive"))
      (node (ref "C803") (pin "2") (pinfunction "2_2") (pintype "passive"))
      (node (ref "C804") (pin "2") (pinfunction "2_2") (pintype "passive"))
      (node (ref "C805") (pin "1") (pinfunction "1_1") (pintype "passive"))
      (node (ref "C806") (pin "1") (pinfunction "1_1") (pintype "passive"))
      (node (ref "C807") (pin "1") (pinfunction "1_1") (pintype "passive"))
      (node (ref "C808") (pin "2") (pinfunction "2_2") (pintype "passive"))
      (node (ref "C809") (pin "1") (pinfunction "1_1") (pintype "passive"))
      (node (ref "C810") (pin "1") (pinfunction "1_1") (pintype "passive"))
      (node (ref "C811") (pin "1") (pinfunction "1_1") (pintype "passive"))
      (node (ref "C812") (pin "1") (pinfunction "1_1") (pintype "passive"))
      (node (ref "C813") (pin "2") (pinfunction "2_2") (pintype "passive"))
      (node (ref "C814") (pin "2") (pinfunction "2_2") (pintype "passive"))
      (node (ref "CN800") (pin "8") (pinfunction "GND_8") (pintype "passive"))
      (node (ref "Q800") (pin "2") (pinfunction "S_2") (pintype "passive"))
      (node (ref "Q801") (pin "2") (pinfunction "S_2") (pintype "passive"))
      (node (ref "Q802") (pin "2") (pinfunction "S_2") (pintype "passive"))
      (node (ref "R819") (pin "1") (pinfunction "1_1") (pintype "passive"))
      (node (ref "R823") (pin "1") (pinfunction "1_1") (pintype "passive"))
      (node (ref "R824") (pin "1") (pinfunction "1_1") (pintype "passive"))
      (node (ref "R829") (pin "1") (pinfunction "1_1") (pintype "passive"))
      (node (ref "R830") (pin "1") (pinfunction "1_1") (pintype "passive"))
      (node (ref "R831") (pin "1") (pinfunction "1_1") (pintype "passive"))
      (node (ref "R832") (pin "1") (pinfunction "1_1") (pintype "passive"))
      (node (ref "R844") (pin "2") (pinfunction "2_2") (pintype "passive"))
      (node (ref "R845") (pin "1") (pinfunction "1_1") (pintype "passive"))
      (node (ref "R846") (pin "1") (pinfunction "1_1") (pintype "passive"))
      (node (ref "R848") (pin "1") (pinfunction "1_1") (pintype "passive"))
      (node (ref "R851") (pin "1") (pinfunction "1_1") (pintype "passive"))
      (node (ref "R854") (pin "1") (pinfunction "1_1") (pintype "passive"))
      (node (ref "U800") (pin "33") (pinfunction "GND_PAD_33") (pintype "passive"))
      (node (ref "U802") (pin "3") (pinfunction "GND_3") (pintype "passive"))
      (node (ref "X800") (pin "2") (pinfunction "GND_2") (pintype "passive"))
      (node (ref "X800") (pin "4") (pinfunction "GND_4") (pintype "passive"))
    )
    (net (code "66") (name "DP3.3VS_A") (class "Default")
      (node (ref "LED800") (pin "4") (pinfunction "Common_Anode_4") (pintype "passive"))
    )
    (net (code "67") (name "DP3.3VS_B") (class "Default")
      (node (ref "C808") (pin "1") (pinfunction "1_1") (pintype "passive"))
      (node (ref "FB800") (pin "1") (pinfunction "1_1") (pintype "passive"))
      (node (ref "R825") (pin "2") (pinfunction "2_2") (pintype "passive"))
      (node (ref "R826") (pin "2") (pinfunction "2_2") (pintype "passive"))
      (node (ref "R827") (pin "2") (pinfunction "2_2") (pintype "passive"))
      (node (ref "R828") (pin "2") (pinfunction "2_2") (pintype "passive"))
      (node (ref "R833") (pin "1") (pinfunction "1_1") (pintype "passive"))
      (node (ref "R835") (pin "1") (pinfunction "1_1") (pintype "passive"))
      (node (ref "U800") (pin "12") (pinfunction "VDDIO_12") (pintype "passive"))
      (node (ref "U802") (pin "5") (pinfunction "VCC_5") (pintype "passive"))
    )
    (net (code "68") (name "DP3.3VS_PHY") (class "Default")
      (node (ref "C800") (pin "1") (pinfunction "1_1") (pintype "passive"))
      (node (ref "C801") (pin "1") (pinfunction "1_1") (pintype "passive"))
      (node (ref "C802") (pin "1") (pinfunction "1_1") (pintype "passive"))
      (node (ref "C813") (pin "1") (pinfunction "1_1") (pintype "passive"))
      (node (ref "C814") (pin "1") (pinfunction "1_1") (pintype "passive"))
      (node (ref "FB800") (pin "2") (pinfunction "2_2") (pintype "passive"))
      (node (ref "R834") (pin "1") (pinfunction "1_1") (pintype "passive"))
      (node (ref "R836") (pin "2") (pinfunction "2_2") (pintype "passive"))
      (node (ref "R837") (pin "2") (pinfunction "2_2") (pintype "passive"))
      (node (ref "R838") (pin "2") (pinfunction "2_2") (pintype "passive"))
      (node (ref "R839") (pin "2") (pinfunction "2_2") (pintype "passive"))
      (node (ref "U800") (pin "1") (pinfunction "VDD2A_1") (pintype "passive"))
      (node (ref "U800") (pin "27") (pinfunction "VDD1A_27") (pintype "passive"))
    )
    (net (code "69") (name "Net-(CN800-GR_K)") (class "Default")
      (node (ref "CN800") (pin "10") (pinfunction "GR_K_10") (pintype "passive"))
      (node (ref "R845") (pin "2") (pinfunction "2_2") (pintype "passive"))
    )
    (net (code "70") (name "Net-(CN800-RD+)") (class "Default")
      (node (ref "CN800") (pin "3") (pinfunction "RD+_3") (pintype "passive"))
      (node (ref "R842") (pin "2") (pinfunction "2_2") (pintype "passive"))
    )
    (net (code "71") (name "Net-(CN800-RD-)") (class "Default")
      (node (ref "CN800") (pin "6") (pinfunction "RD-_6") (pintype "passive"))
      (node (ref "R843") (pin "2") (pinfunction "2_2") (pintype "passive"))
    )
    (net (code "72") (name "Net-(CN800-SH1)") (class "Default")
      (node (ref "CN800") (pin "13") (pinfunction "SH1_13") (pintype "passive"))
      (node (ref "CN800") (pin "14") (pinfunction "SH2_14") (pintype "passive"))
      (node (ref "R844") (pin "1") (pinfunction "1_1") (pintype "passive"))
    )
    (net (code "73") (name "Net-(CN800-TD+)") (class "Default")
      (node (ref "CN800") (pin "1") (pinfunction "TD+_1") (pintype "passive"))
      (node (ref "R840") (pin "2") (pinfunction "2_2") (pintype "passive"))
    )
    (net (code "74") (name "Net-(CN800-TD-)") (class "Default")
      (node (ref "CN800") (pin "2") (pinfunction "TD-_2") (pintype "passive"))
      (node (ref "R841") (pin "2") (pinfunction "2_2") (pintype "passive"))
    )
    (net (code "75") (name "Net-(CN800-YEL_K)") (class "Default")
      (node (ref "CN800") (pin "11") (pinfunction "YEL_K_11") (pintype "passive"))
      (node (ref "R846") (pin "2") (pinfunction "2_2") (pintype "passive"))
    )
    (net (code "76") (name "Net-(LED800-BLUE)") (class "Default")
      (node (ref "LED800") (pin "3") (pinfunction "BLUE_3") (pintype "passive"))
      (node (ref "R847") (pin "1") (pinfunction "1_1") (pintype "passive"))
    )
    (net (code "77") (name "Net-(LED800-GREEN)") (class "Default")
      (node (ref "LED800") (pin "2") (pinfunction "GREEN_2") (pintype "passive"))
      (node (ref "R850") (pin "1") (pinfunction "1_1") (pintype "passive"))
    )
    (net (code "78") (name "Net-(LED800-RED)") (class "Default")
      (node (ref "LED800") (pin "1") (pinfunction "RED_1") (pintype "passive"))
      (node (ref "R853") (pin "1") (pinfunction "1_1") (pintype "passive"))
    )
    (net (code "79") (name "Net-(Q800-G)") (class "Default")
      (node (ref "Q800") (pin "1") (pinfunction "G_1") (pintype "passive"))
      (node (ref "R848") (pin "2") (pinfunction "2_2") (pintype "passive"))
      (node (ref "R849") (pin "2") (pinfunction "2_2") (pintype "passive"))
    )
    (net (code "80") (name "Net-(Q801-G)") (class "Default")
      (node (ref "Q801") (pin "1") (pinfunction "G_1") (pintype "passive"))
      (node (ref "R851") (pin "2") (pinfunction "2_2") (pintype "passive"))
      (node (ref "R852") (pin "2") (pinfunction "2_2") (pintype "passive"))
    )
    (net (code "81") (name "Net-(Q802-G)") (class "Default")
      (node (ref "Q802") (pin "1") (pinfunction "G_1") (pintype "passive"))
      (node (ref "R854") (pin "2") (pinfunction "2_2") (pintype "passive"))
      (node (ref "R855") (pin "2") (pinfunction "2_2") (pintype "passive"))
    )
    (net (code "82") (name "Net-(R822-Pad1)") (class "Default")
      (node (ref "R822") (pin "1") (pinfunction "1_1") (pintype "passive"))
      (node (ref "R823") (pin "2") (pinfunction "2_2") (pintype "passive"))
    )
    (net (code "83") (name "unconnected-(CN800-NC-Pad7)") (class "Default")
      (node (ref "CN800") (pin "7") (pinfunction "NC_7") (pintype "passive+no_connect"))
    )
  )
)
